# LCmeter0-LCD-8pinlcd_1.net
KiCad netlist of a schematic drawn in Altium Designer
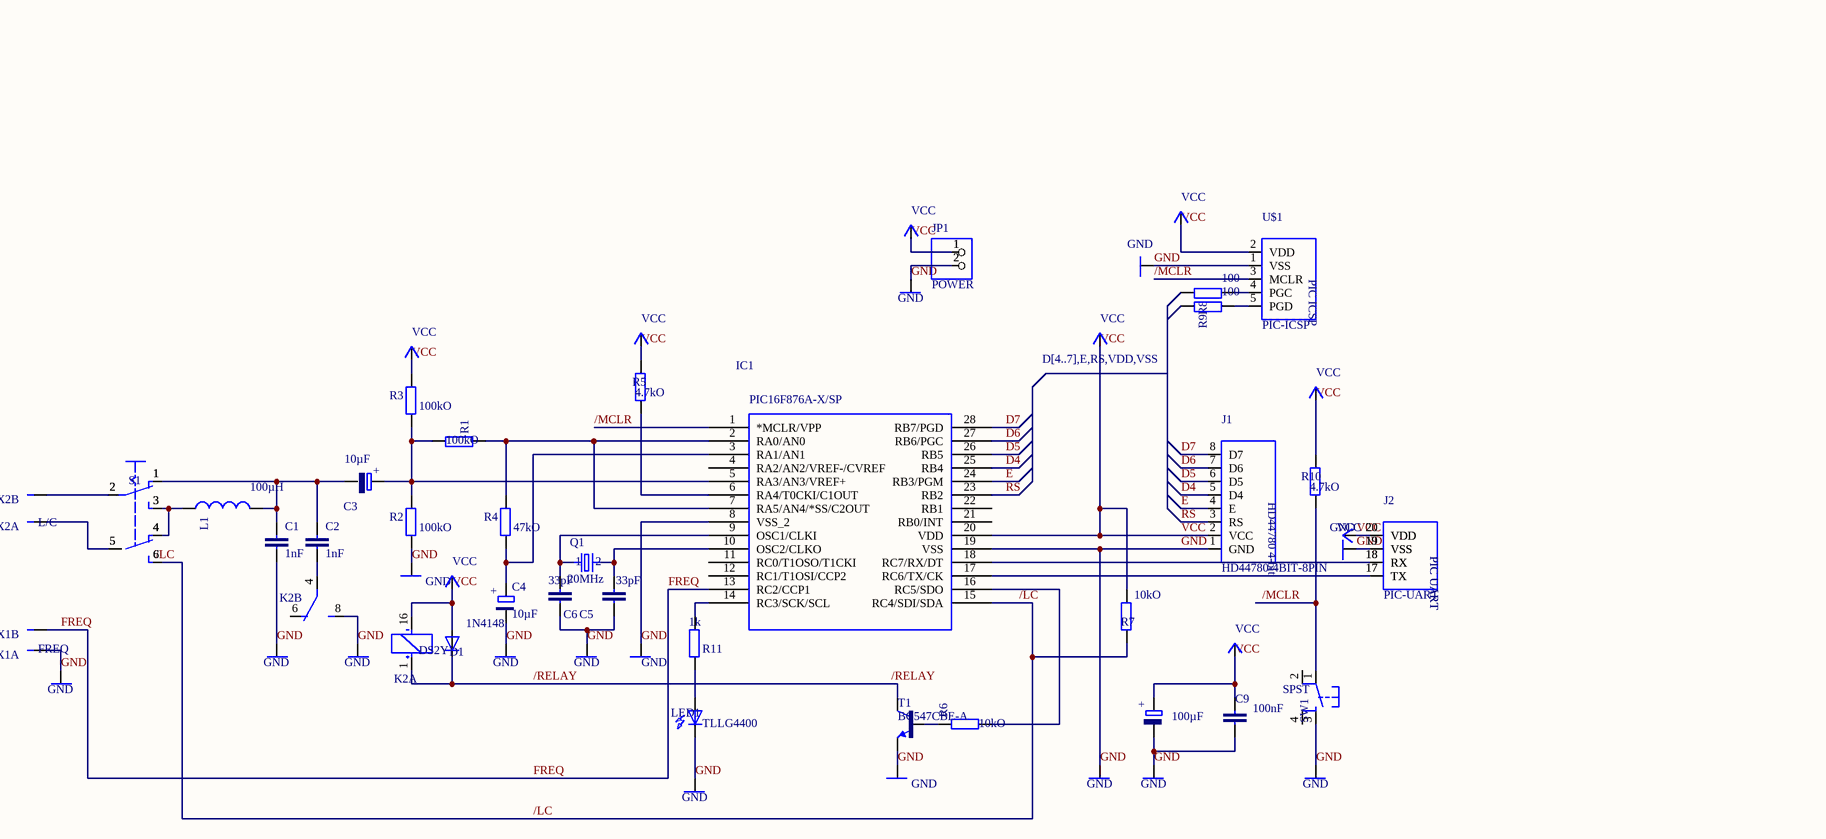
[diagram p0: LCmeter0-LCD-8pinlcd_1.SchDoc]

(export (version "E")
  (design (tool "Eeschema 10.0.6"))
  (components
    (comp (ref "C1") (value "1nF") (footprint "C050-020X036") (libsource (lib "c") (part "C050-020X036")))
    (comp (ref "C2") (value "1nF") (footprint "C050-020X036") (libsource (lib "c") (part "C050-020X036")))
    (comp (ref "C3") (value "10µF") (footprint "E5-4") (libsource (lib "") (part "CPOLE5-4_1")))
    (comp (ref "C4") (value "10µF") (footprint "E5-4") (libsource (lib "c") (part "CPOLE5-4")))
    (comp (ref "C5") (value "33pF") (footprint "C025-020X036") (libsource (lib "c") (part "C025-020X036")))
    (comp (ref "C6") (value "33pF") (footprint "C025-020X036") (libsource (lib "") (part "C025-020X036_1")))
    (comp (ref "C7") (value "100µF") (footprint "E2,5-6") (libsource (lib "c") (part "CPOLE2.5-6")))
    (comp (ref "C9")
      (value "100nF")
      (footprint "C025-024X044")
      (libsource (lib "rcl") (part "C-EU025-024X044"))
    )
    (comp (ref "D1") (value "1N4148") (footprint "DO34-7") (libsource (lib "d") (part "1N414834-7")))
    (comp (ref "GND1") (value "GND") (libsource (lib "") (part "GND_1")))
    (comp (ref "GND2") (value "GND") (libsource (lib "supply1") (part "GND")))
    (comp (ref "GND3") (value "GND") (libsource (lib "supply1") (part "GND")))
    (comp (ref "GND4") (value "GND") (libsource (lib "supply1") (part "GND")))
    (comp (ref "GND5") (value "GND") (libsource (lib "") (part "GND_1")))
    (comp (ref "GND6") (value "GND") (libsource (lib "") (part "GND_1")))
    (comp (ref "GND7") (value "GND") (libsource (lib "") (part "GND_1")))
    (comp (ref "GND8") (value "GND") (libsource (lib "") (part "GND_1")))
    (comp (ref "GND9") (value "GND") (libsource (lib "") (part "GND_1")))
    (comp (ref "GND10") (value "GND") (libsource (lib "supply1") (part "GND")))
    (comp (ref "GND11") (value "GND") (libsource (lib "supply1") (part "GND")))
    (comp (ref "GND12") (value "GND") (libsource (lib "supply1") (part "GND")))
    (comp (ref "GND13") (value "GND") (libsource (lib "supply1") (part "GND")))
    (comp (ref "GND14") (value "GND") (libsource (lib "supply1") (part "GND")))
    (comp (ref "GND15") (value "GND") (libsource (lib "") (part "GND_1")))
    (comp (ref "IC1")
      (value "PIC16F876A-X/SP")
      (footprint "DIL28-3")
      (libsource (lib "mcu") (part "PIC16F876A-X/SP"))
    )
    (comp (ref "J1")
      (value "HD44780-4BIT-8PIN")
      (footprint "CONN-8P")
      (libsource (lib "pinconn") (part "HD44780-4BIT-8PIN"))
    )
    (comp (ref "J2") (value "PIC-UART") (footprint "PIC-UART") (libsource (lib "pinconn") (part "PIC-UART")))
    (comp (ref "JP1") (value "POWER") (footprint "1X02") (libsource (lib "pinhead") (part "PINHD-1X2")))
    (comp (ref "K2") (value "DS2Y") (footprint "DS2Y") (libsource (lib "") (part "DS2Y-S-DC5V_1")))
    (comp (ref "L1") (value "100µH") (footprint "L-02/7") (libsource (lib "r") (part "L02/7")))
    (comp (ref "LED1") (value "TLLG4400") (footprint "LED3MM") (libsource (lib "led") (part "TLLG4400")))
    (comp (ref "P+1") (value "VCC") (libsource (lib "supply1") (part "VCC")))
    (comp (ref "P+2") (value "VCC") (libsource (lib "supply1") (part "VCC")))
    (comp (ref "P+3") (value "VCC") (libsource (lib "") (part "VCC_1")))
    (comp (ref "P+4") (value "VCC") (libsource (lib "supply1") (part "VCC")))
    (comp (ref "P+5") (value "VCC") (libsource (lib "supply1") (part "VCC")))
    (comp (ref "P+6") (value "VCC") (libsource (lib "supply1") (part "VCC")))
    (comp (ref "P+7") (value "VCC") (libsource (lib "supply1") (part "VCC")))
    (comp (ref "P+8") (value "VCC") (libsource (lib "supply1") (part "VCC")))
    (comp (ref "P+9") (value "VCC") (libsource (lib "") (part "VCC_1")))
    (comp (ref "Q1") (value "20MHz") (footprint "HC49") (libsource (lib "q") (part "CRYSTALHC49")))
    (comp (ref "R1") (value "100kO") (footprint "0202/2V") (libsource (lib "") (part "R0202/2V_1")))
    (comp (ref "R2") (value "100kO") (footprint "0202/7") (libsource (lib "") (part "R0202/7_2")))
    (comp (ref "R3") (value "100kO") (footprint "0202/2V") (libsource (lib "r") (part "R0202/2V")))
    (comp (ref "R4") (value "47kO") (footprint "0202/2V") (libsource (lib "r") (part "R0202/2V")))
    (comp (ref "R5") (value "4.7kO") (footprint "0202/7") (libsource (lib "r") (part "R0202/7")))
    (comp (ref "R6") (value "10kO") (footprint "0202/7") (libsource (lib "") (part "R0202/7_1")))
    (comp (ref "R7") (value "10kO") (footprint "0202/10") (libsource (lib "r") (part "R0202/10")))
    (comp (ref "R8") (value "100") (footprint "0202/5") (libsource (lib "r") (part "R0202/5")))
    (comp (ref "R9") (value "100") (footprint "0202/5") (libsource (lib "r") (part "R0202/5")))
    (comp (ref "R10") (value "4.7kO") (footprint "0202/2V") (libsource (lib "") (part "R0202/2V_1")))
    (comp (ref "R11") (value "1k") (footprint "0202/5") (libsource (lib "") (part "R0202/5_1")))
    (comp (ref "S1") (value "~") (footprint "SLSW-2P2T") (libsource (lib "sw") (part "SL-SW-2P-2T")))
    (comp (ref "SW1") (value "SPST") (footprint "PB-5") (libsource (lib "mcu") (part "PB-SPST")))
    (comp (ref "T1") (value "BC547CBE-A") (footprint "TO92-CBE-A") (libsource (lib "t") (part "BC547CBE-A")))
    (comp (ref "U$1") (value "PIC-ICSP") (footprint "CONN-5P") (libsource (lib "pinconn") (part "PIC-ICSP")))
    (comp (ref "X1") (value "FREQ") (footprint "70543-02") (libsource (lib "") (part "C-GRID-02-70543_2")))
    (comp (ref "X2") (value "L/C") (footprint "70543-02") (libsource (lib "") (part "C-GRID-02-70543_1")))
  )
  (nets
    (net (code "1") (name "/D4") (class "Default")
      (node (ref "IC1") (pin "25") (pinfunction "RB4_25") (pintype "passive"))
      (node (ref "J1") (pin "5") (pinfunction "D4_5") (pintype "passive"))
    )
    (net (code "2") (name "/D5") (class "Default")
      (node (ref "IC1") (pin "26") (pinfunction "RB5_26") (pintype "passive"))
      (node (ref "J1") (pin "6") (pinfunction "D5_6") (pintype "passive"))
    )
    (net (code "3") (name "/D6") (class "Default")
      (node (ref "IC1") (pin "27") (pinfunction "RB6/PGC_27") (pintype "passive"))
      (node (ref "J1") (pin "7") (pinfunction "D6_7") (pintype "passive"))
    )
    (net (code "4") (name "/D7") (class "Default")
      (node (ref "IC1") (pin "28") (pinfunction "RB7/PGD_28") (pintype "passive"))
      (node (ref "J1") (pin "8") (pinfunction "D7_8") (pintype "passive"))
    )
    (net (code "5") (name "/E") (class "Default")
      (node (ref "IC1") (pin "24") (pinfunction "RB3/PGM_24") (pintype "passive"))
      (node (ref "J1") (pin "4") (pinfunction "E_4") (pintype "passive"))
    )
    (net (code "6") (name "/FREQ") (class "Default")
      (node (ref "IC1") (pin "13") (pinfunction "RC2/CCP1_13") (pintype "passive"))
      (node (ref "X1") (pin "2") (pinfunction "S_2") (pintype "passive"))
    )
    (net (code "7") (name "/GND") (class "Default")
      (node (ref "C1") (pin "2") (pinfunction "2_2") (pintype "passive"))
      (node (ref "C4") (pin "-") (pinfunction "-_-") (pintype "passive"))
      (node (ref "C5") (pin "1") (pinfunction "1_1") (pintype "passive"))
      (node (ref "C6") (pin "1") (pinfunction "1_1") (pintype "passive"))
      (node (ref "C7") (pin "-") (pinfunction "-_-") (pintype "passive"))
      (node (ref "C9") (pin "2") (pinfunction "2_2") (pintype "passive"))
      (node (ref "GND1") (pin "0") (pinfunction "GND_0") (pintype "passive"))
      (node (ref "GND10") (pin "0") (pinfunction "GND_0") (pintype "passive"))
      (node (ref "GND11") (pin "0") (pinfunction "GND_0") (pintype "passive"))
      (node (ref "GND12") (pin "0") (pinfunction "GND_0") (pintype "passive"))
      (node (ref "GND13") (pin "0") (pinfunction "GND_0") (pintype "passive"))
      (node (ref "GND14") (pin "0") (pinfunction "GND_0") (pintype "passive"))
      (node (ref "GND15") (pin "0") (pinfunction "GND_0") (pintype "passive"))
      (node (ref "GND2") (pin "0") (pinfunction "GND_0") (pintype "passive"))
      (node (ref "GND3") (pin "0") (pinfunction "GND_0") (pintype "passive"))
      (node (ref "GND4") (pin "0") (pinfunction "GND_0") (pintype "passive"))
      (node (ref "GND5") (pin "0") (pinfunction "GND_0") (pintype "passive"))
      (node (ref "GND6") (pin "0") (pinfunction "GND_0") (pintype "passive"))
      (node (ref "GND7") (pin "0") (pinfunction "GND_0") (pintype "passive"))
      (node (ref "GND8") (pin "0") (pinfunction "GND_0") (pintype "passive"))
      (node (ref "GND9") (pin "0") (pinfunction "GND_0") (pintype "passive"))
      (node (ref "IC1") (pin "19") (pinfunction "VSS_19") (pintype "passive"))
      (node (ref "IC1") (pin "8") (pinfunction "VSS_2_8") (pintype "passive"))
      (node (ref "J1") (pin "1") (pinfunction "GND_1") (pintype "passive"))
      (node (ref "J2") (pin "19") (pinfunction "VSS_19") (pintype "passive"))
      (node (ref "JP1") (pin "2") (pinfunction "2_2") (pintype "passive"))
      (node (ref "K2") (pin "8") (pinfunction "S_8") (pintype "passive"))
      (node (ref "LED1") (pin "K") (pinfunction "C_K") (pintype "passive"))
      (node (ref "R2") (pin "1") (pinfunction "1_1") (pintype "passive"))
      (node (ref "SW1") (pin "3") (pinfunction "S_3") (pintype "passive"))
      (node (ref "T1") (pin "E") (pinfunction "E_E") (pintype "passive"))
      (node (ref "U$1") (pin "1") (pinfunction "VSS_1") (pintype "passive"))
      (node (ref "X1") (pin "1") (pinfunction "S_1") (pintype "passive"))
    )
    (net (code "8") (name "/RS") (class "Default")
      (node (ref "IC1") (pin "23") (pinfunction "RB2_23") (pintype "passive"))
      (node (ref "J1") (pin "3") (pinfunction "RS_3") (pintype "passive"))
    )
    (net (code "9") (name "/VCC") (class "Default")
      (node (ref "C7") (pin "+") (pinfunction "+_+") (pintype "passive"))
      (node (ref "C9") (pin "1") (pinfunction "1_1") (pintype "passive"))
      (node (ref "D1") (pin "A") (pinfunction "A_A") (pintype "passive"))
      (node (ref "IC1") (pin "20") (pinfunction "VDD_20") (pintype "passive"))
      (node (ref "J1") (pin "2") (pinfunction "VCC_2") (pintype "passive"))
      (node (ref "J2") (pin "20") (pinfunction "VDD_20") (pintype "passive"))
      (node (ref "JP1") (pin "1") (pinfunction "1_1") (pintype "passive"))
      (node (ref "K2") (pin "16") (pinfunction "-_16") (pintype "passive"))
      (node (ref "P+1") (pin "0") (pinfunction "VCC_0") (pintype "passive"))
      (node (ref "P+2") (pin "0") (pinfunction "VCC_0") (pintype "passive"))
      (node (ref "P+3") (pin "0") (pinfunction "VCC_0") (pintype "passive"))
      (node (ref "P+4") (pin "0") (pinfunction "VCC_0") (pintype "passive"))
      (node (ref "P+5") (pin "0") (pinfunction "VCC_0") (pintype "passive"))
      (node (ref "P+6") (pin "0") (pinfunction "VCC_0") (pintype "passive"))
      (node (ref "P+7") (pin "0") (pinfunction "VCC_0") (pintype "passive"))
      (node (ref "P+8") (pin "0") (pinfunction "VCC_0") (pintype "passive"))
      (node (ref "P+9") (pin "0") (pinfunction "VCC_0") (pintype "passive"))
      (node (ref "R10") (pin "2") (pinfunction "2_2") (pintype "passive"))
      (node (ref "R3") (pin "2") (pinfunction "2_2") (pintype "passive"))
      (node (ref "R5") (pin "2") (pinfunction "2_2") (pintype "passive"))
      (node (ref "R7") (pin "1") (pinfunction "1_1") (pintype "passive"))
      (node (ref "U$1") (pin "2") (pinfunction "VDD_2") (pintype "passive"))
    )
    (net (code "10") (name "/{slash}LC") (class "Default")
      (node (ref "IC1") (pin "15") (pinfunction "RC4/SDI/SDA_15") (pintype "passive"))
      (node (ref "R7") (pin "2") (pinfunction "2_2") (pintype "passive"))
      (node (ref "S1") (pin "6") (pinfunction "S1_6") (pintype "passive"))
    )
    (net (code "11") (name "/{slash}MCLR") (class "Default")
      (node (ref "IC1") (pin "1") (pinfunction "*MCLR/VPP_1") (pintype "passive"))
      (node (ref "R10") (pin "1") (pinfunction "1_1") (pintype "passive"))
      (node (ref "SW1") (pin "1") (pinfunction "P_1") (pintype "passive"))
      (node (ref "U$1") (pin "3") (pinfunction "MCLR_3") (pintype "passive"))
    )
    (net (code "12") (name "/{slash}RELAY") (class "Default")
      (node (ref "D1") (pin "C") (pinfunction "C_C") (pintype "passive"))
      (node (ref "K2") (pin "1") (pinfunction "+_1") (pintype "passive"))
      (node (ref "T1") (pin "C") (pinfunction "C_C") (pintype "passive"))
    )
    (net (code "13") (name "Net-(IC1-OSC1{slash}CLKI)") (class "Default")
      (node (ref "C6") (pin "2") (pinfunction "2_2") (pintype "passive"))
      (node (ref "IC1") (pin "9") (pinfunction "OSC1/CLKI_9") (pintype "passive"))
      (node (ref "Q1") (pin "1") (pinfunction "1_1") (pintype "passive"))
    )
    (net (code "14") (name "Net-(IC1-OSC2{slash}CLKO)") (class "Default")
      (node (ref "C5") (pin "2") (pinfunction "2_2") (pintype "passive"))
      (node (ref "IC1") (pin "10") (pinfunction "OSC2/CLKO_10") (pintype "passive"))
      (node (ref "Q1") (pin "2") (pinfunction "2_2") (pintype "passive"))
    )
    (net (code "15") (name "Net-(IC1-RA0{slash}AN0)") (class "Default")
      (node (ref "IC1") (pin "2") (pinfunction "RA0/AN0_2") (pintype "passive"))
      (node (ref "IC1") (pin "7") (pinfunction "RA5/AN4/*SS/C2OUT_7") (pintype "passive"))
      (node (ref "R1") (pin "2") (pinfunction "2_2") (pintype "passive"))
      (node (ref "R4") (pin "2") (pinfunction "2_2") (pintype "passive"))
    )
    (net (code "16") (name "Net-(IC1-RA1{slash}AN1)") (class "Default")
      (node (ref "C4") (pin "+") (pinfunction "+_+") (pintype "passive"))
      (node (ref "IC1") (pin "3") (pinfunction "RA1/AN1_3") (pintype "passive"))
      (node (ref "R4") (pin "1") (pinfunction "1_1") (pintype "passive"))
    )
    (net (code "17") (name "Net-(IC1-RA3{slash}AN3{slash}VREF+)") (class "Default")
      (node (ref "C3") (pin "+") (pinfunction "+_+") (pintype "passive"))
      (node (ref "IC1") (pin "5") (pinfunction "RA3/AN3/VREF+_5") (pintype "passive"))
      (node (ref "R1") (pin "1") (pinfunction "1_1") (pintype "passive"))
      (node (ref "R2") (pin "2") (pinfunction "2_2") (pintype "passive"))
      (node (ref "R3") (pin "1") (pinfunction "1_1") (pintype "passive"))
    )
    (net (code "18") (name "Net-(IC1-RA4{slash}T0CKI{slash}C1OUT)") (class "Default")
      (node (ref "IC1") (pin "6") (pinfunction "RA4/T0CKI/C1OUT_6") (pintype "passive"))
      (node (ref "R5") (pin "1") (pinfunction "1_1") (pintype "passive"))
    )
    (net (code "19") (name "Net-(IC1-RC3{slash}SCK{slash}SCL)") (class "Default")
      (node (ref "IC1") (pin "14") (pinfunction "RC3/SCK/SCL_14") (pintype "passive"))
      (node (ref "R11") (pin "1") (pinfunction "1_1") (pintype "passive"))
    )
    (net (code "20") (name "Net-(IC1-RC5{slash}SDO)") (class "Default")
      (node (ref "IC1") (pin "16") (pinfunction "RC5/SDO_16") (pintype "passive"))
      (node (ref "R6") (pin "1") (pinfunction "1_1") (pintype "passive"))
    )
    (net (code "21") (name "Net-(IC1-RC6{slash}TX{slash}CK)") (class "Default")
      (node (ref "IC1") (pin "17") (pinfunction "RC6/TX/CK_17") (pintype "passive"))
      (node (ref "J2") (pin "17") (pinfunction "TX_17") (pintype "passive"))
    )
    (net (code "22") (name "Net-(IC1-RC7{slash}RX{slash}DT)") (class "Default")
      (node (ref "IC1") (pin "18") (pinfunction "RC7/RX/DT_18") (pintype "passive"))
      (node (ref "J2") (pin "18") (pinfunction "RX_18") (pintype "passive"))
    )
    (net (code "23") (name "Net-(K2B-P)") (class "Default")
      (node (ref "C2") (pin "2") (pinfunction "2_2") (pintype "passive"))
      (node (ref "K2") (pin "4") (pinfunction "P_4") (pintype "passive"))
    )
    (net (code "24") (name "Net-(LED1-PadA)") (class "Default")
      (node (ref "LED1") (pin "A") (pinfunction "A_A") (pintype "passive"))
      (node (ref "R11") (pin "2") (pinfunction "2_2") (pintype "passive"))
    )
    (net (code "25") (name "Net-(R6-Pad2)") (class "Default")
      (node (ref "R6") (pin "2") (pinfunction "2_2") (pintype "passive"))
      (node (ref "T1") (pin "B") (pinfunction "B_B") (pintype "passive"))
    )
    (net (code "26") (name "Net-(S1-O)") (class "Default")
      (node (ref "C1") (pin "1") (pinfunction "1_1") (pintype "passive"))
      (node (ref "C2") (pin "1") (pinfunction "1_1") (pintype "passive"))
      (node (ref "C3") (pin "-") (pinfunction "-_-") (pintype "passive"))
      (node (ref "L1") (pin "2") (pinfunction "2_2") (pintype "passive"))
      (node (ref "S1") (pin "1") (pinfunction "O_1") (pintype "passive"))
    )
    (net (code "27") (name "Net-(S1-O1)") (class "Default")
      (node (ref "L1") (pin "1") (pinfunction "1_1") (pintype "passive"))
      (node (ref "S1") (pin "3") (pinfunction "S_3") (pintype "passive"))
      (node (ref "S1") (pin "4") (pinfunction "O1_4") (pintype "passive"))
    )
    (net (code "28") (name "Net-(S1-P)") (class "Default")
      (node (ref "S1") (pin "2") (pinfunction "P_2") (pintype "passive"))
      (node (ref "X2") (pin "2") (pinfunction "S_2") (pintype "passive"))
    )
    (net (code "29") (name "Net-(S1-P1)") (class "Default")
      (node (ref "S1") (pin "5") (pinfunction "P1_5") (pintype "passive"))
      (node (ref "X2") (pin "1") (pinfunction "S_1") (pintype "passive"))
    )
    (net (code "30") (name "Net-(U$1-PGC)") (class "Default")
      (node (ref "R8") (pin "1") (pinfunction "1_1") (pintype "passive"))
      (node (ref "U$1") (pin "4") (pinfunction "PGC_4") (pintype "passive"))
    )
    (net (code "31") (name "Net-(U$1-PGD)") (class "Default")
      (node (ref "R9") (pin "1") (pinfunction "1_1") (pintype "passive"))
      (node (ref "U$1") (pin "5") (pinfunction "PGD_5") (pintype "passive"))
    )
    (net (code "32") (name "unconnected-(IC1-RA2{slash}AN2{slash}VREF-{slash}CVREF-Pad4)") (class "Default")
      (node (ref "IC1") (pin "4") (pinfunction "RA2/AN2/VREF-/CVREF_4") (pintype "passive"))
    )
    (net (code "33") (name "unconnected-(IC1-RB0{slash}INT-Pad21)") (class "Default")
      (node (ref "IC1") (pin "21") (pinfunction "RB0/INT_21") (pintype "passive"))
    )
    (net (code "34") (name "unconnected-(IC1-RB1-Pad22)") (class "Default")
      (node (ref "IC1") (pin "22") (pinfunction "RB1_22") (pintype "passive"))
    )
    (net (code "35") (name "unconnected-(IC1-RC0{slash}T1OSO{slash}T1CKI-Pad11)") (class "Default")
      (node (ref "IC1") (pin "11") (pinfunction "RC0/T1OSO/T1CKI_11") (pintype "passive"))
    )
    (net (code "36") (name "unconnected-(IC1-RC1{slash}T1OSI{slash}CCP2-Pad12)") (class "Default")
      (node (ref "IC1") (pin "12") (pinfunction "RC1/T1OSI/CCP2_12") (pintype "passive"))
    )
    (net (code "37") (name "unconnected-(K2B-O-Pad6)") (class "Default")
      (node (ref "K2") (pin "6") (pinfunction "O_6") (pintype "passive"))
    )
    (net (code "38") (name "unconnected-(R8-Pad2)") (class "Default")
      (node (ref "R8") (pin "2") (pinfunction "2_2") (pintype "passive"))
    )
    (net (code "39") (name "unconnected-(R9-Pad2)") (class "Default")
      (node (ref "R9") (pin "2") (pinfunction "2_2") (pintype "passive"))
    )
    (net (code "40") (name "unconnected-(SW1-P1-Pad2)") (class "Default")
      (node (ref "SW1") (pin "2") (pinfunction "P1_2") (pintype "passive"))
    )
    (net (code "41") (name "unconnected-(SW1-S1-Pad4)") (class "Default")
      (node (ref "SW1") (pin "4") (pinfunction "S1_4") (pintype "passive"))
    )
  )
)
